# Power_Input_FET.net
KiCad netlist of a schematic drawn in Altium Designer
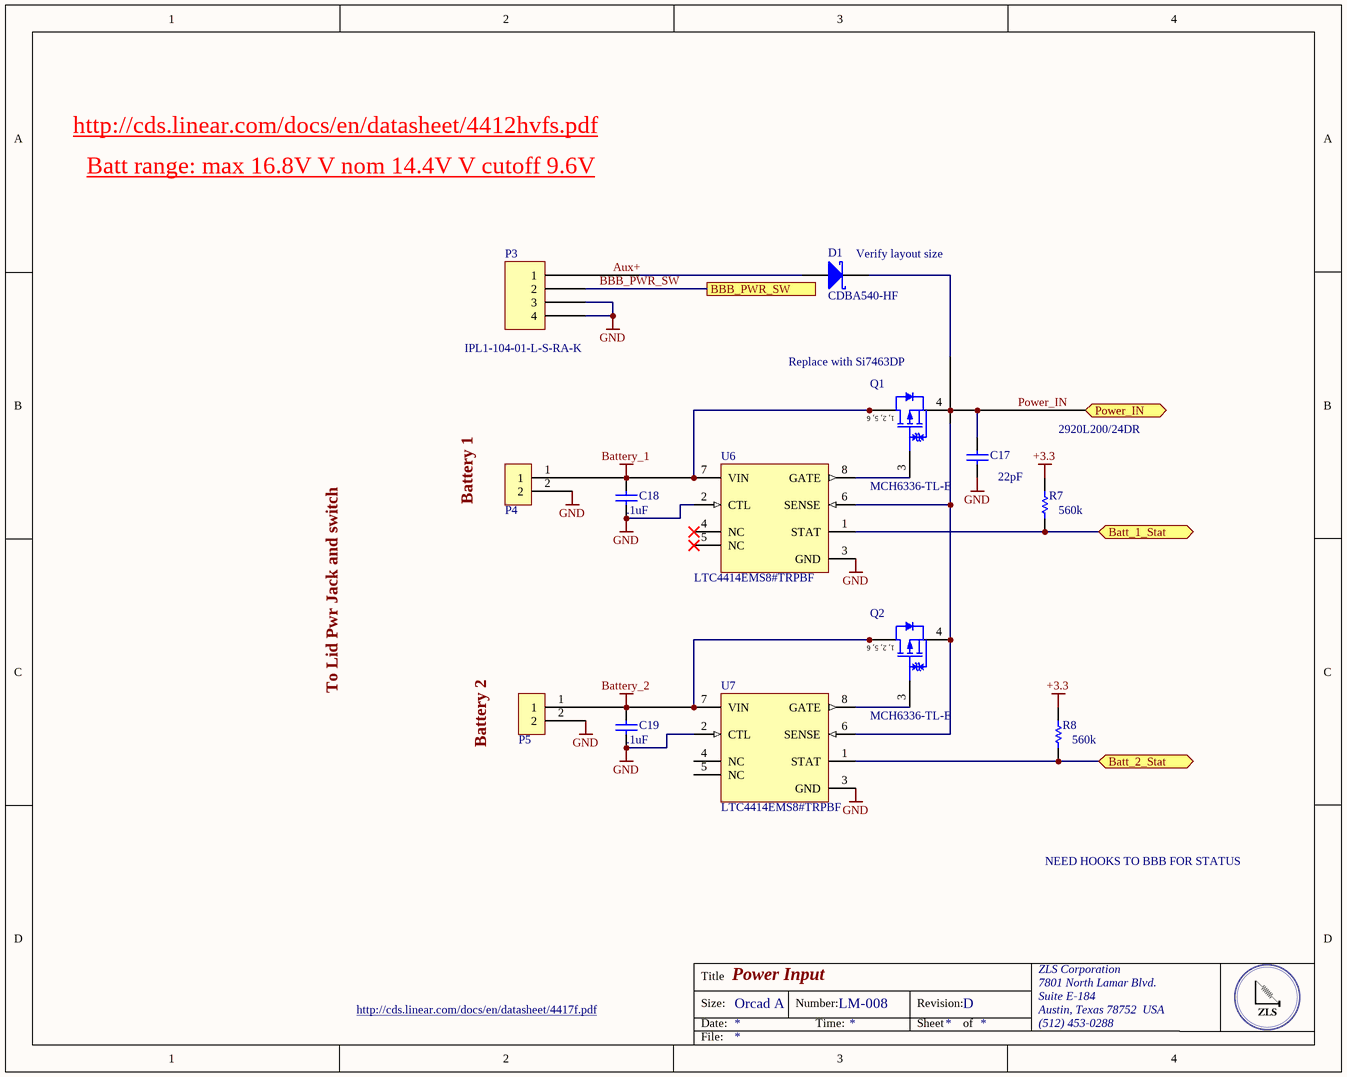
[diagram p0: Power_Input_FET.SchDoc]

(export (version "E")
  (design (tool "Eeschema 10.0.6"))
  (components
    (comp (ref "C17")
      (value "CAP CER 10UF 6.3V X5R 1206")
      (footprint "CAPC1206(3216)130_N")
      (fields
        (field (name "MANUFACTURER") "Taiyo Yuden")
        (field (name "MANUFACTURER PART NUMBER") "JMK316BJ106ML-T")
        (field (name "TOLERANCE") "±20%")
        (field (name "CAPACITANCE") "22pF")
      )
      (libsource (lib "Altium Content Vault") (part "CMP-1037-04913-1"))
    )
    (comp (ref "C18")
      (value "CAP CER 10UF 6.3V X5R 1206")
      (footprint "CAPC1206(3216)130_N")
      (fields
        (field (name "MANUFACTURER") "Taiyo Yuden")
        (field (name "MANUFACTURER PART NUMBER") "JMK316BJ106ML-T")
        (field (name "TOLERANCE") "±20%")
        (field (name "CAPACITANCE") ".1uF")
      )
      (libsource (lib "Altium Content Vault") (part "CMP-1037-04913-1"))
    )
    (comp (ref "C19")
      (value "CAP CER 10UF 6.3V X5R 1206")
      (footprint "CAPC1206(3216)130_N")
      (fields
        (field (name "MANUFACTURER") "Taiyo Yuden")
        (field (name "MANUFACTURER PART NUMBER") "JMK316BJ106ML-T")
        (field (name "TOLERANCE") "±20%")
        (field (name "CAPACITANCE") ".1uF")
      )
      (libsource (lib "Altium Content Vault") (part "CMP-1037-04913-1"))
    )
    (comp (ref "D1")
      (value "CDBA540-HF")
      (footprint "VISH-DO-214AC-2_M")
      (description "DIODE SCHOTTKY 40V 5A DO214AB")
      (fields (field (name "MANUFACTURER") "Comchip Technology"))
      (libsource (lib "Miscellaneous Devices") (part "D Schottky"))
    )
    (comp (ref "P3")
      (value "IPL1-104-01-L-S-RA-K")
      (footprint "IPL1-104-01-L-S-RA-K")
      (fields
        (field (name "MANUFACTURER") "Samtec Inc.")
        (field (name "MANUFACTURER PART NUMBER") "IPL1-104-01-L-S-RA-K")
      )
      (libsource (lib "ZLS_Schematic_lib") (part "IPL1-104-01-L-S-RA-K"))
    )
    (comp (ref "P4")
      (value "IPL1-102-01-F-S-RA-K")
      (footprint "IPL1-102-01-F-S-RA-K")
      (libsource (lib "ZLS_Schematic_lib") (part "IPL1-102-01-F-S-RA-K"))
    )
    (comp (ref "P5")
      (value "IPL1-102-01-F-S-RA-K")
      (footprint "IPL1-102-01-F-S-RA-K")
      (libsource (lib "ZLS_Schematic_lib") (part "IPL1-102-01-F-S-RA-K"))
    )
    (comp (ref "Q1")
      (value "MCH6336-TL-E")
      (footprint "ONSC-MCPH-6_V")
      (description "P-Channel Power MOSFET, -12 V, -5 A, 43 mOhm, Single, 6-Pin MCPH, Pb-Free, Tape and Reel")
      (fields (field (name "MANUFACTURER") "On Semiconductor"))
      (libsource (lib "Altium Content Vault") (part "ONSC-PMOS-6_B"))
    )
    (comp (ref "Q2")
      (value "MCH6336-TL-E")
      (footprint "ONSC-MCPH-6_V")
      (description "P-Channel Power MOSFET, -12 V, -5 A, 43 mOhm, Single, 6-Pin MCPH, Pb-Free, Tape and Reel")
      (fields (field (name "MANUFACTURER") "On Semiconductor"))
      (libsource (lib "Altium Content Vault") (part "ONSC-PMOS-6_B"))
    )
    (comp (ref "R7")
      (value "560k")
      (footprint "RESC0402(1005)_L")
      (fields (field (name "TOLERANCE") "±1%"))
      (libsource (lib "Altium Content Vault") (part "CMP-1011-00927-1"))
    )
    (comp (ref "R8")
      (value "560k")
      (footprint "RESC0402(1005)_L")
      (fields (field (name "TOLERANCE") "±1%"))
      (libsource (lib "Altium Content Vault") (part "CMP-1011-00927-1"))
    )
    (comp (ref "U6")
      (value "LTC4414EMS8#TRPBF")
      (footprint "LT-MS8-8_L")
      (fields (field (name "MANUFACTURER") "Linear Technology"))
      (libsource (lib "Altium Content Vault") (part "CMP-0479-00214-1"))
    )
    (comp (ref "U7")
      (value "LTC4414EMS8#TRPBF")
      (footprint "LT-MS8-8_L")
      (fields (field (name "MANUFACTURER") "Linear Technology"))
      (libsource (lib "Altium Content Vault") (part "CMP-0479-00214-1"))
    )
  )
  (nets
    (net (code "1") (name "+3.3") (class "Default")
      (node (ref "R7") (pin "2") (pinfunction "2_2") (pintype "passive"))
      (node (ref "R8") (pin "2") (pinfunction "2_2") (pintype "passive"))
    )
    (net (code "2") (name "/Aux+") (class "Default")
      (node (ref "D1") (pin "1") (pinfunction "A_1") (pintype "passive"))
      (node (ref "P3") (pin "1") (pinfunction "1_1") (pintype "passive"))
    )
    (net (code "3") (name "/BBB_PWR_SW") (class "Default")
      (node (ref "P3") (pin "2") (pinfunction "2_2") (pintype "passive"))
    )
    (net (code "4") (name "/Batt_1_Stat") (class "Default")
      (node (ref "R7") (pin "1") (pinfunction "1_1") (pintype "passive"))
      (node (ref "U6") (pin "1") (pinfunction "STAT_1") (pintype "open_collector"))
    )
    (net (code "5") (name "/Batt_2_Stat") (class "Default")
      (node (ref "R8") (pin "1") (pinfunction "1_1") (pintype "passive"))
      (node (ref "U7") (pin "1") (pinfunction "STAT_1") (pintype "open_collector"))
    )
    (net (code "6") (name "/Power_IN") (class "Default")
      (node (ref "C17") (pin "2") (pinfunction "2_2") (pintype "passive"))
      (node (ref "D1") (pin "2") (pinfunction "K_2") (pintype "passive"))
      (node (ref "Q1") (pin "4") (pinfunction "S_4") (pintype "passive"))
      (node (ref "Q2") (pin "4") (pinfunction "S_4") (pintype "passive"))
      (node (ref "U6") (pin "6") (pinfunction "SENSE_6") (pintype "input"))
      (node (ref "U7") (pin "6") (pinfunction "SENSE_6") (pintype "input"))
    )
    (net (code "7") (name "Battery_1") (class "Default")
      (node (ref "C18") (pin "2") (pinfunction "2_2") (pintype "passive"))
      (node (ref "P4") (pin "1") (pinfunction "1_1") (pintype "passive"))
      (node (ref "Q1") (pin "1") (pinfunction "D_1") (pintype "passive"))
      (node (ref "Q1") (pin "2") (pinfunction "D_2") (pintype "passive"))
      (node (ref "Q1") (pin "5") (pinfunction "D_5") (pintype "passive"))
      (node (ref "Q1") (pin "6") (pinfunction "D_6") (pintype "passive"))
      (node (ref "U6") (pin "7") (pinfunction "VIN_7") (pintype "power_in"))
    )
    (net (code "8") (name "Battery_2") (class "Default")
      (node (ref "C19") (pin "2") (pinfunction "2_2") (pintype "passive"))
      (node (ref "P5") (pin "1") (pinfunction "1_1") (pintype "passive"))
      (node (ref "Q2") (pin "1") (pinfunction "D_1") (pintype "passive"))
      (node (ref "Q2") (pin "2") (pinfunction "D_2") (pintype "passive"))
      (node (ref "Q2") (pin "5") (pinfunction "D_5") (pintype "passive"))
      (node (ref "Q2") (pin "6") (pinfunction "D_6") (pintype "passive"))
      (node (ref "U7") (pin "7") (pinfunction "VIN_7") (pintype "power_in"))
    )
    (net (code "9") (name "GND") (class "Default")
      (node (ref "C17") (pin "1") (pinfunction "1_1") (pintype "passive"))
      (node (ref "C18") (pin "1") (pinfunction "1_1") (pintype "passive"))
      (node (ref "C19") (pin "1") (pinfunction "1_1") (pintype "passive"))
      (node (ref "P3") (pin "3") (pinfunction "3_3") (pintype "passive"))
      (node (ref "P3") (pin "4") (pinfunction "4_4") (pintype "passive"))
      (node (ref "P4") (pin "2") (pinfunction "2_2") (pintype "passive"))
      (node (ref "P5") (pin "2") (pinfunction "2_2") (pintype "passive"))
      (node (ref "U6") (pin "2") (pinfunction "CTL_2") (pintype "input"))
      (node (ref "U6") (pin "3") (pinfunction "GND_3") (pintype "power_in"))
      (node (ref "U7") (pin "2") (pinfunction "CTL_2") (pintype "input"))
      (node (ref "U7") (pin "3") (pinfunction "GND_3") (pintype "power_in"))
    )
    (net (code "10") (name "Net-(Q1-G)") (class "Default")
      (node (ref "Q1") (pin "3") (pinfunction "G_3") (pintype "passive"))
      (node (ref "U6") (pin "8") (pinfunction "GATE_8") (pintype "output"))
    )
    (net (code "11") (name "Net-(Q2-G)") (class "Default")
      (node (ref "Q2") (pin "3") (pinfunction "G_3") (pintype "passive"))
      (node (ref "U7") (pin "8") (pinfunction "GATE_8") (pintype "output"))
    )
    (net (code "12") (name "unconnected-(U6-NC-Pad4)") (class "Default")
      (node (ref "U6") (pin "4") (pinfunction "NC_4") (pintype "passive+no_connect"))
    )
    (net (code "13") (name "unconnected-(U6-NC-Pad5)") (class "Default")
      (node (ref "U6") (pin "5") (pinfunction "NC_5") (pintype "passive+no_connect"))
    )
    (net (code "14") (name "unconnected-(U7-NC-Pad4)") (class "Default")
      (node (ref "U7") (pin "4") (pinfunction "NC_4") (pintype "passive"))
    )
    (net (code "15") (name "unconnected-(U7-NC-Pad5)") (class "Default")
      (node (ref "U7") (pin "5") (pinfunction "NC_5") (pintype "passive"))
    )
  )
)
